# Bat_Protection.net
KiCad netlist of a schematic drawn in Altium Designer
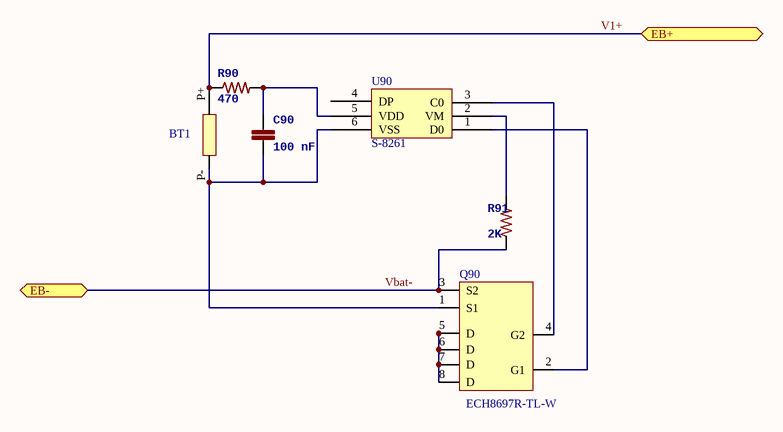
[diagram p0: Bat_Protection.SchDoc]

(export (version "E")
  (design (tool "Eeschema 10.0.6"))
  (components
    (comp (ref "BT1")
      (value "Battery")
      (footprint "Battery-Li-ion")
      (libsource (lib "yusend_power") (part "Battery"))
    )
    (comp (ref "C90")
      (value "100 nF")
      (footprint "0805")
      (fields
        (field (name "MANUFACTURER") "Kemet")
        (field (name "MANUFACTURER PART NUMBER") "C0805C105K8RACTU")
        (field (name "TOLERANCE") "±10%")
      )
      (libsource (lib "yusend_power") (part "CAP0805_100nF"))
    )
    (comp (ref "Q90")
      (value "ECH8697R-TL-W")
      (footprint "SOT-28FL/ECH8")
      (fields (field (name "MANUF PART NO") "ECH8697R-TL-W"))
      (libsource (lib "yusend_power") (part "ECH8697R-TL-W"))
    )
    (comp (ref "R90")
      (value "470")
      (footprint "0805")
      (fields
        (field (name "MANUFACTURER") "TE Connectivity")
        (field (name "MANUFACTURER PART NUMBER") "1625856-2")
        (field (name "TOLERANCE") "±10%")
      )
      (libsource (lib "yusend_power") (part "RES_0805_470"))
    )
    (comp (ref "R91")
      (value "2K")
      (footprint "0805")
      (fields
        (field (name "MANUFACTURER") "TE Connectivity")
        (field (name "MANUFACTURER PART NUMBER") "1625856-2")
        (field (name "TOLERANCE") "±10%")
      )
      (libsource (lib "yusend_power") (part "RES_0805_2K"))
    )
    (comp (ref "U90")
      (value "S-8261")
      (footprint "SOT236-A-PKG")
      (libsource (lib "yusend_power") (part "S-8261"))
    )
  )
  (nets
    (net (code "1") (name "/V1+") (class "Default")
      (node (ref "BT1") (pin "P+") (pinfunction "P+_P+") (pintype "power_in"))
      (node (ref "R90") (pin "1") (pinfunction "1_1") (pintype "passive"))
    )
    (net (code "2") (name "/Vbat-") (class "Default")
      (node (ref "Q90") (pin "3") (pinfunction "S2_3") (pintype "passive"))
      (node (ref "R91") (pin "1") (pinfunction "1_1") (pintype "passive"))
    )
    (net (code "3") (name "Net-(Q90-D-Pad5)") (class "Default")
      (node (ref "Q90") (pin "5") (pinfunction "D_5") (pintype "passive"))
      (node (ref "Q90") (pin "6") (pinfunction "D_6") (pintype "passive"))
      (node (ref "Q90") (pin "7") (pinfunction "D_7") (pintype "passive"))
      (node (ref "Q90") (pin "8") (pinfunction "D_8") (pintype "passive"))
    )
    (net (code "4") (name "Net-(Q90-G1)") (class "Default")
      (node (ref "Q90") (pin "2") (pinfunction "G1_2") (pintype "passive"))
      (node (ref "U90") (pin "1") (pinfunction "D0_1") (pintype "passive"))
    )
    (net (code "5") (name "Net-(Q90-G2)") (class "Default")
      (node (ref "Q90") (pin "4") (pinfunction "G2_4") (pintype "passive"))
      (node (ref "U90") (pin "3") (pinfunction "C0_3") (pintype "passive"))
    )
    (net (code "6") (name "Net-(Q90-S1)") (class "Default")
      (node (ref "BT1") (pin "P-") (pinfunction "P-_P-") (pintype "power_in"))
      (node (ref "C90") (pin "2") (pinfunction "2_2") (pintype "passive"))
      (node (ref "Q90") (pin "1") (pinfunction "S1_1") (pintype "passive"))
      (node (ref "U90") (pin "6") (pinfunction "VSS_6") (pintype "passive"))
    )
    (net (code "7") (name "Net-(U90-VDD)") (class "Default")
      (node (ref "C90") (pin "1") (pinfunction "1_1") (pintype "passive"))
      (node (ref "R90") (pin "2") (pinfunction "2_2") (pintype "passive"))
      (node (ref "U90") (pin "5") (pinfunction "VDD_5") (pintype "passive"))
    )
    (net (code "8") (name "Net-(U90-VM)") (class "Default")
      (node (ref "R91") (pin "2") (pinfunction "2_2") (pintype "passive"))
      (node (ref "U90") (pin "2") (pinfunction "VM_2") (pintype "passive"))
    )
    (net (code "9") (name "unconnected-(U90-DP-Pad4)") (class "Default")
      (node (ref "U90") (pin "4") (pinfunction "DP_4") (pintype "passive"))
    )
  )
)
